# Power_PMIC.net
KiCad netlist of a schematic drawn in Altium Designer
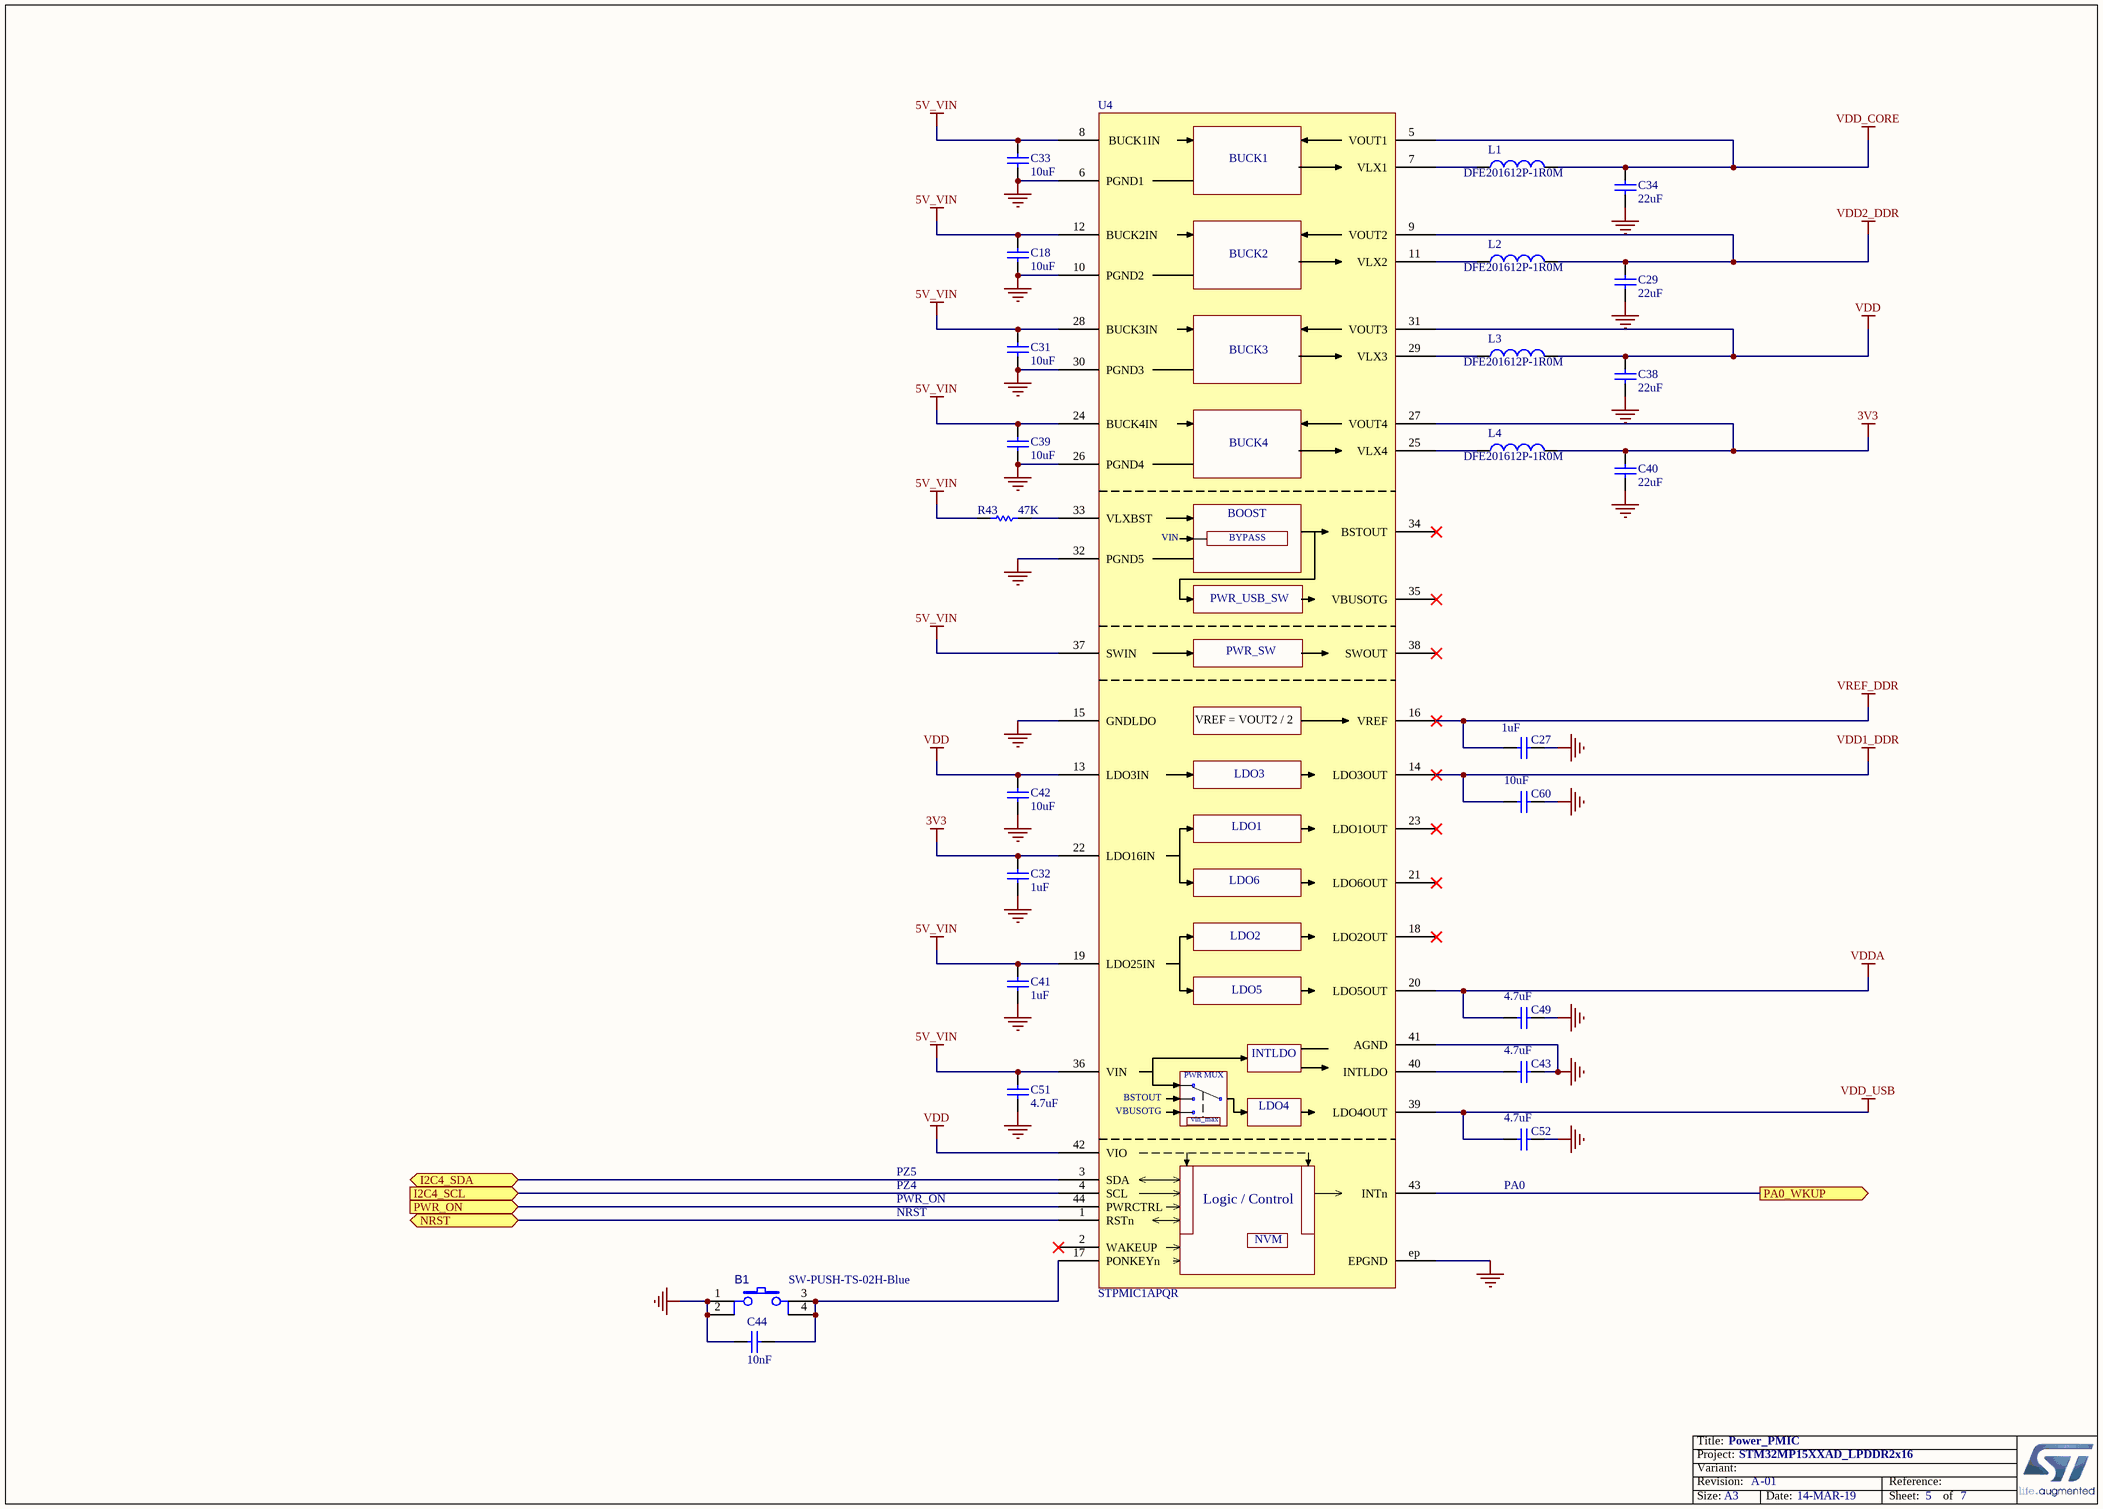
[diagram p0: Power_PMIC.SchDoc]

(export (version "E")
  (design (tool "Eeschema 10.0.6"))
  (components
    (comp (ref "B1")
      (value "SW-PUSH-TS-02H-Blue")
      (footprint "SWI_JIUBABA_C-TS-02H-2-5-B-V-T_R_BLUE")
      (description "Switch HW SMD blue")
      (fields
        (field (name "INTERNAL_PART_NUMBER") "MCD-00172")
        (field (name "MANUFACTURER_PART_NUMBER") "C-TS-02H-2.5-B-V-T/R BLUE")
        (field (name "PROVIDED_BY") "SUBCO")
      )
      (libsource (lib "MCD_PARTS_database") (part "SW-PUSH-TS-02H-Blue"))
    )
    (comp (ref "C18")
      (value "10uF")
      (footprint "C0603")
      (description "Capacitor, MLCC, 10uF, 10V, X5R, 10%, 0603, T=0,8mm")
      (fields
        (field (name "INTERNAL_PART_NUMBER") "MCD-00099")
        (field (name "MANUFACTURER_PART_NUMBER") "GRM188R61A106KE69D")
        (field (name "PROVIDED_BY") "SUBCO")
      )
      (libsource (lib "MCD_PARTS_database") (part "Capacitor"))
    )
    (comp (ref "C27")
      (value "1uF")
      (footprint "C0402")
      (description "Capacitor, MLCC, 1uF, 25V, X5R, 10%, 0402, T=0,5mm")
      (fields
        (field (name "INTERNAL_PART_NUMBER") "MCD-00095")
        (field (name "MANUFACTURER_PART_NUMBER") "GRM155R61E105KA12")
        (field (name "PROVIDED_BY") "SUBCO")
      )
      (libsource (lib "MCD_PARTS_database") (part "Capacitor"))
    )
    (comp (ref "C29")
      (value "22uF")
      (footprint "C0603")
      (description "Capacitor, MLCC, 22uF, 6V3, X5R, 20%, 0603, T=0,8mm")
      (fields
        (field (name "INTERNAL_PART_NUMBER") "MCD-00100")
        (field (name "MANUFACTURER_PART_NUMBER") "GRM188R60J226MEA0J")
        (field (name "PROVIDED_BY") "SUBCO")
      )
      (libsource (lib "MCD_PARTS_database") (part "Capacitor"))
    )
    (comp (ref "C31")
      (value "10uF")
      (footprint "C0603")
      (description "Capacitor, MLCC, 10uF, 10V, X5R, 10%, 0603, T=0,8mm")
      (fields
        (field (name "INTERNAL_PART_NUMBER") "MCD-00099")
        (field (name "MANUFACTURER_PART_NUMBER") "GRM188R61A106KE69D")
        (field (name "PROVIDED_BY") "SUBCO")
      )
      (libsource (lib "MCD_PARTS_database") (part "Capacitor"))
    )
    (comp (ref "C32")
      (value "1uF")
      (footprint "C0402")
      (description "Capacitor, MLCC, 1uF, 25V, X5R, 10%, 0402, T=0,5mm")
      (fields
        (field (name "INTERNAL_PART_NUMBER") "MCD-00095")
        (field (name "MANUFACTURER_PART_NUMBER") "GRM155R61E105KA12")
        (field (name "PROVIDED_BY") "SUBCO")
      )
      (libsource (lib "MCD_PARTS_database") (part "Capacitor"))
    )
    (comp (ref "C33")
      (value "10uF")
      (footprint "C0603")
      (description "Capacitor, MLCC, 10uF, 10V, X5R, 10%, 0603, T=0,8mm")
      (fields
        (field (name "INTERNAL_PART_NUMBER") "MCD-00099")
        (field (name "MANUFACTURER_PART_NUMBER") "GRM188R61A106KE69D")
        (field (name "PROVIDED_BY") "SUBCO")
      )
      (libsource (lib "MCD_PARTS_database") (part "Capacitor"))
    )
    (comp (ref "C34")
      (value "22uF")
      (footprint "C0603")
      (description "Capacitor, MLCC, 22uF, 6V3, X5R, 20%, 0603, T=0,8mm")
      (fields
        (field (name "INTERNAL_PART_NUMBER") "MCD-00100")
        (field (name "MANUFACTURER_PART_NUMBER") "GRM188R60J226MEA0J")
        (field (name "PROVIDED_BY") "SUBCO")
      )
      (libsource (lib "MCD_PARTS_database") (part "Capacitor"))
    )
    (comp (ref "C38")
      (value "22uF")
      (footprint "C0603")
      (description "Capacitor, MLCC, 22uF, 6V3, X5R, 20%, 0603, T=0,8mm")
      (fields
        (field (name "INTERNAL_PART_NUMBER") "MCD-00100")
        (field (name "MANUFACTURER_PART_NUMBER") "GRM188R60J226MEA0J")
        (field (name "PROVIDED_BY") "SUBCO")
      )
      (libsource (lib "MCD_PARTS_database") (part "Capacitor"))
    )
    (comp (ref "C39")
      (value "10uF")
      (footprint "C0603")
      (description "Capacitor, MLCC, 10uF, 10V, X5R, 10%, 0603, T=0,8mm")
      (fields
        (field (name "INTERNAL_PART_NUMBER") "MCD-00099")
        (field (name "MANUFACTURER_PART_NUMBER") "GRM188R61A106KE69D")
        (field (name "PROVIDED_BY") "SUBCO")
      )
      (libsource (lib "MCD_PARTS_database") (part "Capacitor"))
    )
    (comp (ref "C40")
      (value "22uF")
      (footprint "C0603")
      (description "Capacitor, MLCC, 22uF, 6V3, X5R, 20%, 0603, T=0,8mm")
      (fields
        (field (name "INTERNAL_PART_NUMBER") "MCD-00100")
        (field (name "MANUFACTURER_PART_NUMBER") "GRM188R60J226MEA0J")
        (field (name "PROVIDED_BY") "SUBCO")
      )
      (libsource (lib "MCD_PARTS_database") (part "Capacitor"))
    )
    (comp (ref "C41")
      (value "1uF")
      (footprint "C0402")
      (description "Capacitor, MLCC, 1uF, 25V, X5R, 10%, 0402, T=0,5mm")
      (fields
        (field (name "INTERNAL_PART_NUMBER") "MCD-00095")
        (field (name "MANUFACTURER_PART_NUMBER") "GRM155R61E105KA12")
        (field (name "PROVIDED_BY") "SUBCO")
      )
      (libsource (lib "MCD_PARTS_database") (part "Capacitor"))
    )
    (comp (ref "C42")
      (value "10uF")
      (footprint "C0603")
      (description "Capacitor, MLCC, 10uF, 10V, X5R, 10%, 0603, T=0,8mm")
      (fields
        (field (name "INTERNAL_PART_NUMBER") "MCD-00099")
        (field (name "MANUFACTURER_PART_NUMBER") "GRM188R61A106KE69D")
        (field (name "PROVIDED_BY") "SUBCO")
      )
      (libsource (lib "MCD_PARTS_database") (part "Capacitor"))
    )
    (comp (ref "C43")
      (value "4.7uF")
      (footprint "C0402")
      (description "Capacitor, MLCC, 4.7uF, 6V3, X5R, 20%, 0402, T=0,5mm")
      (fields
        (field (name "INTERNAL_PART_NUMBER") "MCD-01356")
        (field (name "MANUFACTURER_PART_NUMBER") "GRM155R60J475ME47")
        (field (name "PROVIDED_BY") "SUBCO")
      )
      (libsource (lib "MCD_PARTS_database") (part "Capacitor"))
    )
    (comp (ref "C44")
      (value "10nF")
      (footprint "C0402")
      (description "Capacitor, MLCC, 10nF, 16V, X7R, 10%, 0402, T=0.5mm")
      (fields
        (field (name "INTERNAL_PART_NUMBER") "MCD-00011")
        (field (name "MANUFACTURER_PART_NUMBER") "CC0402KRX7R7BB103")
        (field (name "PROVIDED_BY") "SUBCO")
      )
      (libsource (lib "MCD_PARTS_database") (part "Capacitor"))
    )
    (comp (ref "C49")
      (value "4.7uF")
      (footprint "C0402")
      (description "Capacitor, MLCC, 4.7uF, 6V3, X5R, 20%, 0402, T=0,5mm")
      (fields
        (field (name "INTERNAL_PART_NUMBER") "MCD-01356")
        (field (name "MANUFACTURER_PART_NUMBER") "GRM155R60J475ME47")
        (field (name "PROVIDED_BY") "SUBCO")
      )
      (libsource (lib "MCD_PARTS_database") (part "Capacitor"))
    )
    (comp (ref "C51")
      (value "4.7uF")
      (footprint "C0402")
      (description "Capacitor, MLCC, 4.7uF, 6V3, X5R, 20%, 0402, T=0,5mm")
      (fields
        (field (name "INTERNAL_PART_NUMBER") "MCD-01356")
        (field (name "MANUFACTURER_PART_NUMBER") "GRM155R60J475ME47")
        (field (name "PROVIDED_BY") "SUBCO")
      )
      (libsource (lib "MCD_PARTS_database") (part "Capacitor"))
    )
    (comp (ref "C52")
      (value "4.7uF")
      (footprint "C0402")
      (description "Capacitor, MLCC, 4.7uF, 6V3, X5R, 20%, 0402, T=0,5mm")
      (fields
        (field (name "INTERNAL_PART_NUMBER") "MCD-01356")
        (field (name "MANUFACTURER_PART_NUMBER") "GRM155R60J475ME47")
        (field (name "PROVIDED_BY") "SUBCO")
      )
      (libsource (lib "MCD_PARTS_database") (part "Capacitor"))
    )
    (comp (ref "C60")
      (value "10uF")
      (footprint "C0603")
      (description "Capacitor, MLCC, 10uF, 10V, X5R, 10%, 0603, T=0,8mm")
      (fields
        (field (name "INTERNAL_PART_NUMBER") "MCD-00099")
        (field (name "MANUFACTURER_PART_NUMBER") "GRM188R61A106KE69D")
        (field (name "PROVIDED_BY") "SUBCO")
      )
      (libsource (lib "MCD_PARTS_database") (part "Capacitor"))
    )
    (comp (ref "L1")
      (value "DFE201612P-1R0M")
      (footprint "IND_MURATA_DFE201612P")
      (description "Inductors 1.0uH 54mOhms3.3A +/-20% 2016")
      (fields
        (field (name "INTERNAL_PART_NUMBER") "MCD-01491")
        (field (name "MANUFACTURER") "MURATA")
        (field (name "PROVIDED_BY") "SUBCO")
      )
      (libsource (lib "MCD_PARTS_database") (part "Inductor"))
    )
    (comp (ref "L2")
      (value "DFE201612P-1R0M")
      (footprint "IND_MURATA_DFE201612P")
      (description "Inductors 1.0uH 54mOhms3.3A +/-20% 2016")
      (fields
        (field (name "INTERNAL_PART_NUMBER") "MCD-01491")
        (field (name "MANUFACTURER") "MURATA")
        (field (name "PROVIDED_BY") "SUBCO")
      )
      (libsource (lib "MCD_PARTS_database") (part "Inductor"))
    )
    (comp (ref "L3")
      (value "DFE201612P-1R0M")
      (footprint "IND_MURATA_DFE201612P")
      (description "Inductors 1.0uH 54mOhms3.3A +/-20% 2016")
      (fields
        (field (name "INTERNAL_PART_NUMBER") "MCD-01491")
        (field (name "MANUFACTURER") "MURATA")
        (field (name "PROVIDED_BY") "SUBCO")
      )
      (libsource (lib "MCD_PARTS_database") (part "Inductor"))
    )
    (comp (ref "L4")
      (value "DFE201612P-1R0M")
      (footprint "IND_MURATA_DFE201612P")
      (description "Inductors 1.0uH 54mOhms3.3A +/-20% 2016")
      (fields
        (field (name "INTERNAL_PART_NUMBER") "MCD-01491")
        (field (name "MANUFACTURER") "MURATA")
        (field (name "PROVIDED_BY") "SUBCO")
      )
      (libsource (lib "MCD_PARTS_database") (part "Inductor"))
    )
    (comp (ref "R43")
      (value "47K")
      (footprint "R0402")
      (description "Resistor,47K,0402,1%,1/16W")
      (fields
        (field (name "INTERNAL_PART_NUMBER") "MCD-00063")
        (field (name "MANUFACTURER_PART_NUMBER") "RC0402FR-0747KL")
        (field (name "PROVIDED_BY") "SUBCO")
      )
      (libsource (lib "MCD_PARTS_database") (part "Resistor"))
    )
    (comp (ref "U4")
      (value "STPMIC1APQR")
      (footprint "ICC_WFQFN44-EPAD_5X6_P040")
      (fields
        (field (name "INTERNAL_PART_NUMBER") "MCD-01650")
        (field (name "MANUFACTURER") "STMICROELECTRONICS")
        (field (name "BMS_PART_NUMBER") "9177723")
        (field (name "PROVIDED_BY") "SUBCO with ST control")
      )
      (libsource (lib "MCD_PARTS_database") (part "STPMU1"))
    )
  )
  (nets
    (net (code "1") (name "/I2C4_SCL") (class "Default")
      (node (ref "U4") (pin "4") (pinfunction "SCL_4") (pintype "passive"))
    )
    (net (code "2") (name "/I2C4_SDA") (class "Default")
      (node (ref "U4") (pin "3") (pinfunction "SDA_3") (pintype "passive"))
    )
    (net (code "3") (name "/NRST") (class "Default")
      (node (ref "U4") (pin "1") (pinfunction "RSTn_1") (pintype "passive"))
    )
    (net (code "4") (name "/PA0_WKUP") (class "Default")
      (node (ref "U4") (pin "43") (pinfunction "INTn_43") (pintype "passive"))
    )
    (net (code "5") (name "/PWR_ON") (class "Default")
      (node (ref "U4") (pin "44") (pinfunction "PWRCTRL_44") (pintype "passive"))
    )
    (net (code "6") (name "3V3") (class "Default")
      (node (ref "C32") (pin "2") (pinfunction "2_2") (pintype "passive"))
      (node (ref "C40") (pin "2") (pinfunction "2_2") (pintype "passive"))
      (node (ref "L4") (pin "2") (pinfunction "2_2") (pintype "passive"))
      (node (ref "U4") (pin "22") (pinfunction "LDO16IN_22") (pintype "passive"))
      (node (ref "U4") (pin "27") (pinfunction "VOUT4_27") (pintype "passive"))
    )
    (net (code "7") (name "5V_VIN") (class "Default")
      (node (ref "C18") (pin "2") (pinfunction "2_2") (pintype "passive"))
      (node (ref "C31") (pin "2") (pinfunction "2_2") (pintype "passive"))
      (node (ref "C33") (pin "2") (pinfunction "2_2") (pintype "passive"))
      (node (ref "C39") (pin "2") (pinfunction "2_2") (pintype "passive"))
      (node (ref "C41") (pin "2") (pinfunction "2_2") (pintype "passive"))
      (node (ref "C51") (pin "1") (pinfunction "1_1") (pintype "passive"))
      (node (ref "R43") (pin "2") (pinfunction "2_2") (pintype "passive"))
      (node (ref "U4") (pin "12") (pinfunction "BUCK2IN_12") (pintype "passive"))
      (node (ref "U4") (pin "19") (pinfunction "LDO25IN_19") (pintype "passive"))
      (node (ref "U4") (pin "24") (pinfunction "BUCK4IN_24") (pintype "passive"))
      (node (ref "U4") (pin "28") (pinfunction "BUCK3IN_28") (pintype "passive"))
      (node (ref "U4") (pin "36") (pinfunction "VIN_36") (pintype "passive"))
      (node (ref "U4") (pin "37") (pinfunction "SWIN_37") (pintype "passive"))
      (node (ref "U4") (pin "8") (pinfunction "BUCK1IN_8") (pintype "passive"))
    )
    (net (code "8") (name "GND") (class "Default")
      (node (ref "B1") (pin "1") (pinfunction "1_1") (pintype "passive"))
      (node (ref "B1") (pin "2") (pinfunction "2_2") (pintype "passive"))
      (node (ref "C18") (pin "1") (pinfunction "1_1") (pintype "passive"))
      (node (ref "C27") (pin "1") (pinfunction "1_1") (pintype "passive"))
      (node (ref "C29") (pin "1") (pinfunction "1_1") (pintype "passive"))
      (node (ref "C31") (pin "1") (pinfunction "1_1") (pintype "passive"))
      (node (ref "C32") (pin "1") (pinfunction "1_1") (pintype "passive"))
      (node (ref "C33") (pin "1") (pinfunction "1_1") (pintype "passive"))
      (node (ref "C34") (pin "1") (pinfunction "1_1") (pintype "passive"))
      (node (ref "C38") (pin "1") (pinfunction "1_1") (pintype "passive"))
      (node (ref "C39") (pin "1") (pinfunction "1_1") (pintype "passive"))
      (node (ref "C40") (pin "1") (pinfunction "1_1") (pintype "passive"))
      (node (ref "C41") (pin "1") (pinfunction "1_1") (pintype "passive"))
      (node (ref "C42") (pin "1") (pinfunction "1_1") (pintype "passive"))
      (node (ref "C43") (pin "1") (pinfunction "1_1") (pintype "passive"))
      (node (ref "C44") (pin "1") (pinfunction "1_1") (pintype "passive"))
      (node (ref "C49") (pin "1") (pinfunction "1_1") (pintype "passive"))
      (node (ref "C51") (pin "2") (pinfunction "2_2") (pintype "passive"))
      (node (ref "C52") (pin "1") (pinfunction "1_1") (pintype "passive"))
      (node (ref "C60") (pin "1") (pinfunction "1_1") (pintype "passive"))
      (node (ref "U4") (pin "10") (pinfunction "PGND2_10") (pintype "passive"))
      (node (ref "U4") (pin "15") (pinfunction "GNDLDO_15") (pintype "passive"))
      (node (ref "U4") (pin "26") (pinfunction "PGND4_26") (pintype "passive"))
      (node (ref "U4") (pin "30") (pinfunction "PGND3_30") (pintype "passive"))
      (node (ref "U4") (pin "32") (pinfunction "PGND5_32") (pintype "passive"))
      (node (ref "U4") (pin "41") (pinfunction "AGND_41") (pintype "passive"))
      (node (ref "U4") (pin "6") (pinfunction "PGND1_6") (pintype "passive"))
      (node (ref "U4") (pin "ep") (pinfunction "EPGND_ep") (pintype "passive"))
    )
    (net (code "9") (name "Net-(U4-INTLDO)") (class "Default")
      (node (ref "C43") (pin "2") (pinfunction "2_2") (pintype "passive"))
      (node (ref "U4") (pin "40") (pinfunction "INTLDO_40") (pintype "passive"))
    )
    (net (code "10") (name "Net-(U4-PONKEYn)") (class "Default")
      (node (ref "B1") (pin "3") (pinfunction "3_3") (pintype "passive"))
      (node (ref "B1") (pin "4") (pinfunction "4_4") (pintype "passive"))
      (node (ref "C44") (pin "2") (pinfunction "2_2") (pintype "passive"))
      (node (ref "U4") (pin "17") (pinfunction "PONKEYn_17") (pintype "passive"))
    )
    (net (code "11") (name "Net-(U4-VLX1)") (class "Default")
      (node (ref "L1") (pin "1") (pinfunction "1_1") (pintype "passive"))
      (node (ref "U4") (pin "7") (pinfunction "VLX1_7") (pintype "passive"))
    )
    (net (code "12") (name "Net-(U4-VLX2)") (class "Default")
      (node (ref "L2") (pin "1") (pinfunction "1_1") (pintype "passive"))
      (node (ref "U4") (pin "11") (pinfunction "VLX2_11") (pintype "passive"))
    )
    (net (code "13") (name "Net-(U4-VLX3)") (class "Default")
      (node (ref "L3") (pin "1") (pinfunction "1_1") (pintype "passive"))
      (node (ref "U4") (pin "29") (pinfunction "VLX3_29") (pintype "passive"))
    )
    (net (code "14") (name "Net-(U4-VLX4)") (class "Default")
      (node (ref "L4") (pin "1") (pinfunction "1_1") (pintype "passive"))
      (node (ref "U4") (pin "25") (pinfunction "VLX4_25") (pintype "passive"))
    )
    (net (code "15") (name "Net-(U4-VLXBST)") (class "Default")
      (node (ref "R43") (pin "1") (pinfunction "1_1") (pintype "passive"))
      (node (ref "U4") (pin "33") (pinfunction "VLXBST_33") (pintype "passive"))
    )
    (net (code "16") (name "VDD") (class "Default")
      (node (ref "C38") (pin "2") (pinfunction "2_2") (pintype "passive"))
      (node (ref "C42") (pin "2") (pinfunction "2_2") (pintype "passive"))
      (node (ref "L3") (pin "2") (pinfunction "2_2") (pintype "passive"))
      (node (ref "U4") (pin "13") (pinfunction "LDO3IN_13") (pintype "passive"))
      (node (ref "U4") (pin "31") (pinfunction "VOUT3_31") (pintype "passive"))
      (node (ref "U4") (pin "42") (pinfunction "VIO_42") (pintype "passive"))
    )
    (net (code "17") (name "VDD1_DDR") (class "Default")
      (node (ref "C60") (pin "2") (pinfunction "2_2") (pintype "passive"))
      (node (ref "U4") (pin "14") (pinfunction "LDO3OUT_14") (pintype "passive"))
    )
    (net (code "18") (name "VDD2_DDR") (class "Default")
      (node (ref "C29") (pin "2") (pinfunction "2_2") (pintype "passive"))
      (node (ref "L2") (pin "2") (pinfunction "2_2") (pintype "passive"))
      (node (ref "U4") (pin "9") (pinfunction "VOUT2_9") (pintype "passive"))
    )
    (net (code "19") (name "VDDA") (class "Default")
      (node (ref "C49") (pin "2") (pinfunction "2_2") (pintype "passive"))
      (node (ref "U4") (pin "20") (pinfunction "LDO5OUT_20") (pintype "passive"))
    )
    (net (code "20") (name "VDD_CORE") (class "Default")
      (node (ref "C34") (pin "2") (pinfunction "2_2") (pintype "passive"))
      (node (ref "L1") (pin "2") (pinfunction "2_2") (pintype "passive"))
      (node (ref "U4") (pin "5") (pinfunction "VOUT1_5") (pintype "passive"))
    )
    (net (code "21") (name "VDD_USB") (class "Default")
      (node (ref "C52") (pin "2") (pinfunction "2_2") (pintype "passive"))
      (node (ref "U4") (pin "39") (pinfunction "LDO4OUT_39") (pintype "passive"))
    )
    (net (code "22") (name "VREF_DDR") (class "Default")
      (node (ref "C27") (pin "2") (pinfunction "2_2") (pintype "passive"))
      (node (ref "U4") (pin "16") (pinfunction "VREF_16") (pintype "passive"))
    )
    (net (code "23") (name "unconnected-(U4-BSTOUT-Pad34)") (class "Default")
      (node (ref "U4") (pin "34") (pinfunction "BSTOUT_34") (pintype "passive+no_connect"))
    )
    (net (code "24") (name "unconnected-(U4-LDO1OUT-Pad23)") (class "Default")
      (node (ref "U4") (pin "23") (pinfunction "LDO1OUT_23") (pintype "passive+no_connect"))
    )
    (net (code "25") (name "unconnected-(U4-LDO2OUT-Pad18)") (class "Default")
      (node (ref "U4") (pin "18") (pinfunction "LDO2OUT_18") (pintype "passive+no_connect"))
    )
    (net (code "26") (name "unconnected-(U4-LDO6OUT-Pad21)") (class "Default")
      (node (ref "U4") (pin "21") (pinfunction "LDO6OUT_21") (pintype "passive+no_connect"))
    )
    (net (code "27") (name "unconnected-(U4-SWOUT-Pad38)") (class "Default")
      (node (ref "U4") (pin "38") (pinfunction "SWOUT_38") (pintype "passive+no_connect"))
    )
    (net (code "28") (name "unconnected-(U4-VBUSOTG-Pad35)") (class "Default")
      (node (ref "U4") (pin "35") (pinfunction "VBUSOTG_35") (pintype "passive+no_connect"))
    )
    (net (code "29") (name "unconnected-(U4-WAKEUP-Pad2)") (class "Default")
      (node (ref "U4") (pin "2") (pinfunction "WAKEUP_2") (pintype "passive+no_connect"))
    )
  )
)
